# PNP_Cell.net
KiCad netlist of a schematic drawn in Altium Designer
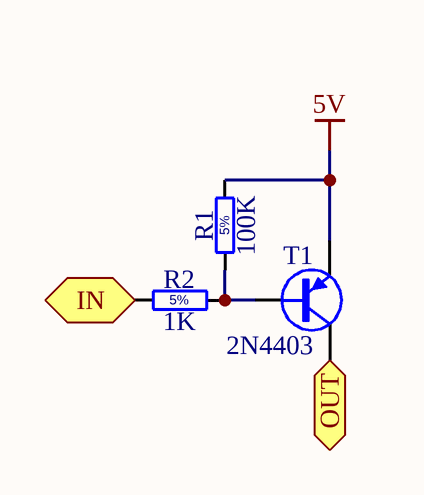
[diagram p0: PNP_Cell.SchDoc]

(export (version "E")
  (design (tool "Eeschema 10.0.6"))
  (components
    (comp (ref "R1")
      (value "100K")
      (footprint "RES_ARCOL_RCC025")
      (description "Resistor - 5%")
      (fields
        (field (name "PART NUMBER") "RCF_5K1_5%_0.25W_+10-6PPM_ARCOL_RCC025")
        (field (name "POWER") "0.25W")
        (field (name "AUTHOR") "CERN DEM JLC")
      )
      (libsource (lib "Resistors") (part "Resistor - 5%"))
    )
    (comp (ref "R2")
      (value "1K")
      (footprint "RES_ARCOL_RCC025")
      (description "Resistor - 5%")
      (fields
        (field (name "PART NUMBER") "RCF_5K1_5%_0.25W_+10-6PPM_ARCOL_RCC025")
        (field (name "POWER") "0.25W")
        (field (name "AUTHOR") "CERN DEM JLC")
      )
      (libsource (lib "Resistors") (part "Resistor - 5%"))
    )
    (comp (ref "T1")
      (value "2N4403")
      (footprint "TO-92AA-P254")
      (description "PNP Transistor")
      (fields
        (field (name "PART NUMBER") "2N3906RL1G")
        (field (name "MANUFACTURER") "ON SEMICONDUCTOR")
        (field (name "AUTHOR") "CERN DEM JLC")
      )
      (libsource (lib "ICs And Semiconductors") (part "PNP E1 B2 C3"))
    )
  )
  (nets
    (net (code "1") (name "/IN") (class "Default")
      (node (ref "R2") (pin "1") (pinfunction "1_1") (pintype "passive"))
    )
    (net (code "2") (name "/OUT") (class "Default")
      (node (ref "T1") (pin "3") (pinfunction "C_3") (pintype "passive"))
    )
    (net (code "3") (name "5V") (class "Default")
      (node (ref "R1") (pin "2") (pinfunction "2_2") (pintype "passive"))
      (node (ref "T1") (pin "1") (pinfunction "E_1") (pintype "passive"))
    )
    (net (code "4") (name "Net-(T1-B)") (class "Default")
      (node (ref "R1") (pin "1") (pinfunction "1_1") (pintype "passive"))
      (node (ref "R2") (pin "2") (pinfunction "2_2") (pintype "passive"))
      (node (ref "T1") (pin "2") (pinfunction "B_2") (pintype "passive"))
    )
  )
)
